# Server_I2C_GND.net
KiCad netlist of a schematic drawn in Altium Designer
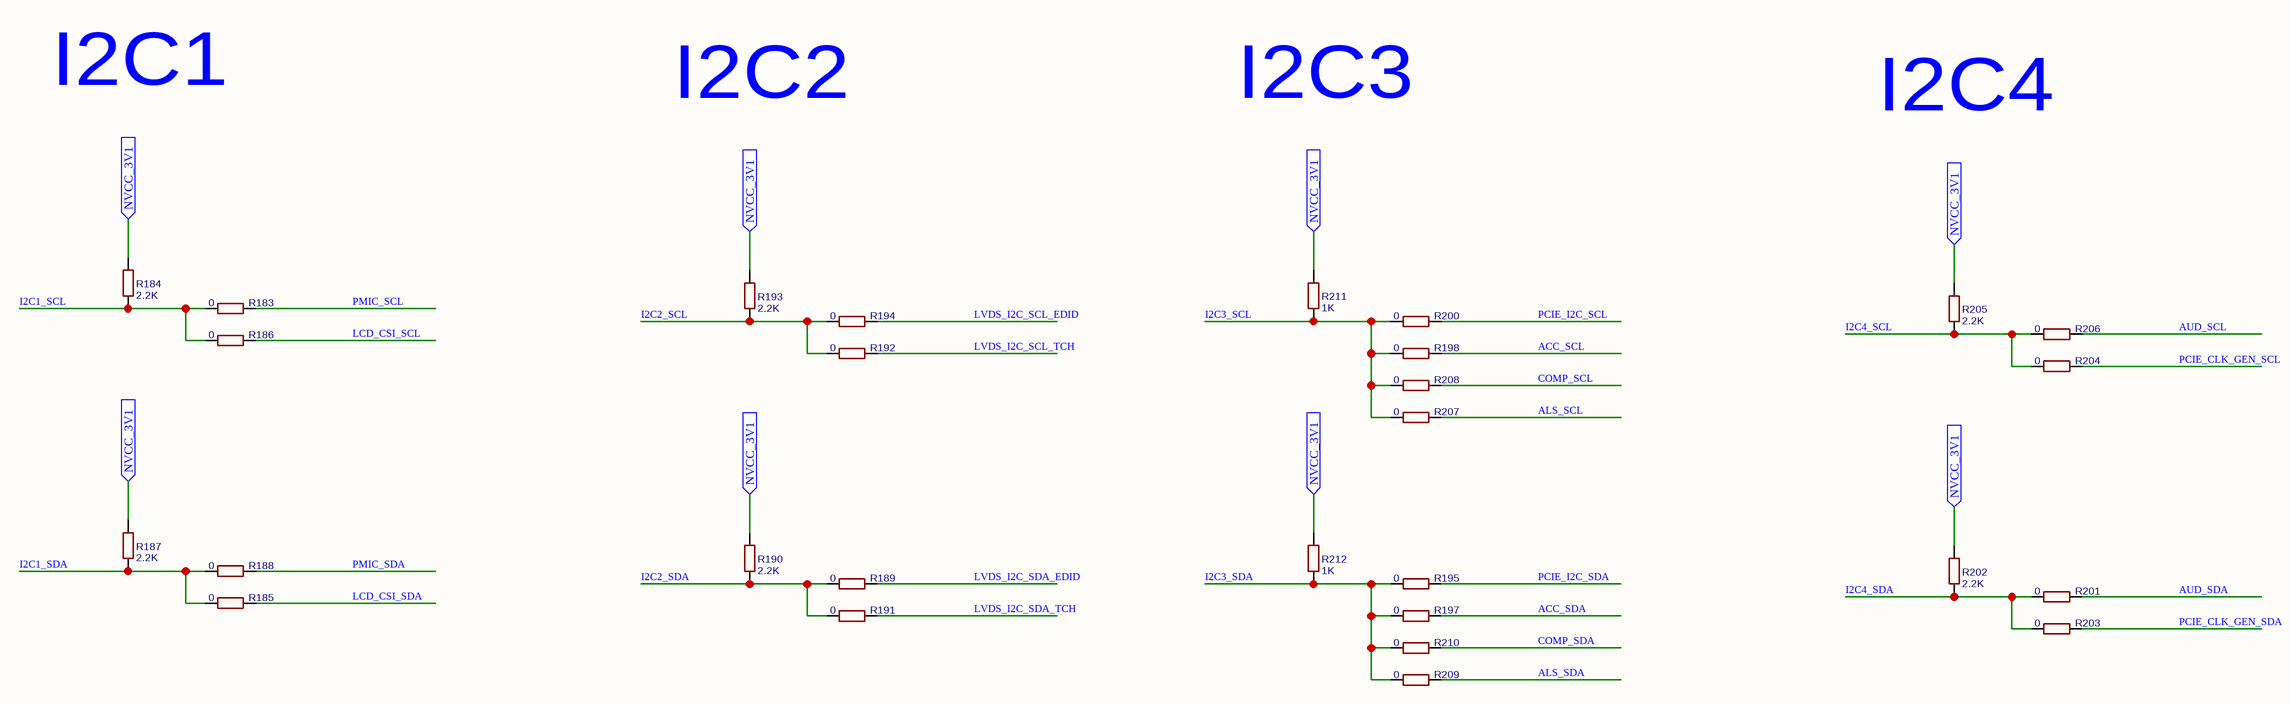
[diagram p0: Server I2C & GND.schdoc]

(export (version "E")
  (design (tool "Eeschema 10.0.6"))
  (components
    (comp (ref "R183")
      (value "0")
      (fields
        (field (name "BOM_MANUFACTURER PART") "RK73Z1ETTP")
        (field (name "BOM_SUPPLIER PART") "C131359")
      )
      (libsource (lib "altium-import") (part "root_0_0_"))
    )
    (comp (ref "R184")
      (value "2.2K")
      (fields
        (field (name "BOM_MANUFACTURER PART") "0402WGF2201TCE")
        (field (name "BOM_SUPPLIER PART") "C25879")
      )
      (libsource (lib "altium-import") (part "root_1_2.2K_"))
    )
    (comp (ref "R185")
      (value "0")
      (fields
        (field (name "BOM_MANUFACTURER PART") "RK73Z1ETTP")
        (field (name "BOM_SUPPLIER PART") "C131359")
      )
      (libsource (lib "altium-import") (part "root_0_0_"))
    )
    (comp (ref "R186")
      (value "0")
      (fields
        (field (name "BOM_MANUFACTURER PART") "RK73Z1ETTP")
        (field (name "BOM_SUPPLIER PART") "C131359")
      )
      (libsource (lib "altium-import") (part "root_0_0_"))
    )
    (comp (ref "R187")
      (value "2.2K")
      (fields
        (field (name "BOM_MANUFACTURER PART") "0402WGF2201TCE")
        (field (name "BOM_SUPPLIER PART") "C25879")
      )
      (libsource (lib "altium-import") (part "root_1_2.2K_"))
    )
    (comp (ref "R188")
      (value "0")
      (fields
        (field (name "BOM_MANUFACTURER PART") "RK73Z1ETTP")
        (field (name "BOM_SUPPLIER PART") "C131359")
      )
      (libsource (lib "altium-import") (part "root_0_0_"))
    )
    (comp (ref "R189")
      (value "0")
      (fields
        (field (name "BOM_MANUFACTURER PART") "RK73Z1ETTP")
        (field (name "BOM_SUPPLIER PART") "C131359")
      )
      (libsource (lib "altium-import") (part "root_0_0_"))
    )
    (comp (ref "R190")
      (value "2.2K")
      (fields
        (field (name "BOM_MANUFACTURER PART") "0402WGF2201TCE")
        (field (name "BOM_SUPPLIER PART") "C25879")
      )
      (libsource (lib "altium-import") (part "root_1_2.2K_"))
    )
    (comp (ref "R191")
      (value "0")
      (fields
        (field (name "BOM_MANUFACTURER PART") "RK73Z1ETTP")
        (field (name "BOM_SUPPLIER PART") "C131359")
      )
      (libsource (lib "altium-import") (part "root_0_0_"))
    )
    (comp (ref "R192")
      (value "0")
      (fields
        (field (name "BOM_MANUFACTURER PART") "RK73Z1ETTP")
        (field (name "BOM_SUPPLIER PART") "C131359")
      )
      (libsource (lib "altium-import") (part "root_0_0_"))
    )
    (comp (ref "R193")
      (value "2.2K")
      (fields
        (field (name "BOM_MANUFACTURER PART") "0402WGF2201TCE")
        (field (name "BOM_SUPPLIER PART") "C25879")
      )
      (libsource (lib "altium-import") (part "root_1_2.2K_"))
    )
    (comp (ref "R194")
      (value "0")
      (fields
        (field (name "BOM_MANUFACTURER PART") "RK73Z1ETTP")
        (field (name "BOM_SUPPLIER PART") "C131359")
      )
      (libsource (lib "altium-import") (part "root_0_0_"))
    )
    (comp (ref "R195")
      (value "0")
      (fields
        (field (name "BOM_MANUFACTURER PART") "RK73Z1ETTP")
        (field (name "BOM_SUPPLIER PART") "C131359")
      )
      (libsource (lib "altium-import") (part "root_0_0_"))
    )
    (comp (ref "R197")
      (value "0")
      (fields
        (field (name "BOM_MANUFACTURER PART") "RK73Z1ETTP")
        (field (name "BOM_SUPPLIER PART") "C131359")
      )
      (libsource (lib "altium-import") (part "root_0_0_"))
    )
    (comp (ref "R198")
      (value "0")
      (fields
        (field (name "BOM_MANUFACTURER PART") "RK73Z1ETTP")
        (field (name "BOM_SUPPLIER PART") "C131359")
      )
      (libsource (lib "altium-import") (part "root_0_0_"))
    )
    (comp (ref "R200")
      (value "0")
      (fields
        (field (name "BOM_MANUFACTURER PART") "RK73Z1ETTP")
        (field (name "BOM_SUPPLIER PART") "C131359")
      )
      (libsource (lib "altium-import") (part "root_0_0_"))
    )
    (comp (ref "R201")
      (value "0")
      (fields
        (field (name "BOM_MANUFACTURER PART") "RK73Z1ETTP")
        (field (name "BOM_SUPPLIER PART") "C131359")
      )
      (libsource (lib "altium-import") (part "root_0_0_"))
    )
    (comp (ref "R202")
      (value "2.2K")
      (fields
        (field (name "BOM_MANUFACTURER PART") "0402WGF2201TCE")
        (field (name "BOM_SUPPLIER PART") "C25879")
      )
      (libsource (lib "altium-import") (part "root_1_2.2K_"))
    )
    (comp (ref "R203")
      (value "0")
      (fields
        (field (name "BOM_MANUFACTURER PART") "RK73Z1ETTP")
        (field (name "BOM_SUPPLIER PART") "C131359")
      )
      (libsource (lib "altium-import") (part "root_0_0_"))
    )
    (comp (ref "R204")
      (value "0")
      (fields
        (field (name "BOM_MANUFACTURER PART") "RK73Z1ETTP")
        (field (name "BOM_SUPPLIER PART") "C131359")
      )
      (libsource (lib "altium-import") (part "root_0_0_"))
    )
    (comp (ref "R205")
      (value "2.2K")
      (fields
        (field (name "BOM_MANUFACTURER PART") "0402WGF2201TCE")
        (field (name "BOM_SUPPLIER PART") "C25879")
      )
      (libsource (lib "altium-import") (part "root_1_2.2K_"))
    )
    (comp (ref "R206")
      (value "0")
      (fields
        (field (name "BOM_MANUFACTURER PART") "RK73Z1ETTP")
        (field (name "BOM_SUPPLIER PART") "C131359")
      )
      (libsource (lib "altium-import") (part "root_0_0_"))
    )
    (comp (ref "R207")
      (value "0")
      (fields
        (field (name "BOM_MANUFACTURER PART") "RK73Z1ETTP")
        (field (name "BOM_SUPPLIER PART") "C131359")
      )
      (libsource (lib "altium-import") (part "root_0_0_"))
    )
    (comp (ref "R208")
      (value "0")
      (fields
        (field (name "BOM_MANUFACTURER PART") "RK73Z1ETTP")
        (field (name "BOM_SUPPLIER PART") "C131359")
      )
      (libsource (lib "altium-import") (part "root_0_0_"))
    )
    (comp (ref "R209")
      (value "0")
      (fields
        (field (name "BOM_MANUFACTURER PART") "RK73Z1ETTP")
        (field (name "BOM_SUPPLIER PART") "C131359")
      )
      (libsource (lib "altium-import") (part "root_0_0_"))
    )
    (comp (ref "R210")
      (value "0")
      (fields
        (field (name "BOM_MANUFACTURER PART") "RK73Z1ETTP")
        (field (name "BOM_SUPPLIER PART") "C131359")
      )
      (libsource (lib "altium-import") (part "root_0_0_"))
    )
    (comp (ref "R211")
      (value "1K")
      (fields
        (field (name "BOM_MANUFACTURER PART") "0402WGF1001TCE")
        (field (name "BOM_SUPPLIER PART") "C11702")
      )
      (libsource (lib "altium-import") (part "root_1_1K_"))
    )
    (comp (ref "R212")
      (value "1K")
      (fields
        (field (name "BOM_MANUFACTURER PART") "0402WGF1001TCE")
        (field (name "BOM_SUPPLIER PART") "C11702")
      )
      (libsource (lib "altium-import") (part "root_1_1K_"))
    )
  )
  (nets
    (net (code "1") (name "/ACC_SCL") (class "Default")
      (node (ref "R198") (pin "2") (pinfunction "2_2") (pintype "passive"))
    )
    (net (code "2") (name "/ACC_SDA") (class "Default")
      (node (ref "R197") (pin "2") (pinfunction "2_2") (pintype "passive"))
    )
    (net (code "3") (name "/ALS_SCL") (class "Default")
      (node (ref "R207") (pin "2") (pinfunction "2_2") (pintype "passive"))
    )
    (net (code "4") (name "/ALS_SDA") (class "Default")
      (node (ref "R209") (pin "2") (pinfunction "2_2") (pintype "passive"))
    )
    (net (code "5") (name "/AUD_SCL") (class "Default")
      (node (ref "R206") (pin "2") (pinfunction "2_2") (pintype "passive"))
    )
    (net (code "6") (name "/AUD_SDA") (class "Default")
      (node (ref "R201") (pin "2") (pinfunction "2_2") (pintype "passive"))
    )
    (net (code "7") (name "/COMP_SCL") (class "Default")
      (node (ref "R208") (pin "2") (pinfunction "2_2") (pintype "passive"))
    )
    (net (code "8") (name "/COMP_SDA") (class "Default")
      (node (ref "R210") (pin "2") (pinfunction "2_2") (pintype "passive"))
    )
    (net (code "9") (name "/I2C1_SCL") (class "Default")
      (node (ref "R183") (pin "1") (pinfunction "1_1") (pintype "passive"))
      (node (ref "R184") (pin "1") (pinfunction "1_1") (pintype "passive"))
      (node (ref "R186") (pin "1") (pinfunction "1_1") (pintype "passive"))
    )
    (net (code "10") (name "/I2C1_SDA") (class "Default")
      (node (ref "R185") (pin "1") (pinfunction "1_1") (pintype "passive"))
      (node (ref "R187") (pin "1") (pinfunction "1_1") (pintype "passive"))
      (node (ref "R188") (pin "1") (pinfunction "1_1") (pintype "passive"))
    )
    (net (code "11") (name "/I2C2_SCL") (class "Default")
      (node (ref "R192") (pin "1") (pinfunction "1_1") (pintype "passive"))
      (node (ref "R193") (pin "1") (pinfunction "1_1") (pintype "passive"))
      (node (ref "R194") (pin "1") (pinfunction "1_1") (pintype "passive"))
    )
    (net (code "12") (name "/I2C2_SDA") (class "Default")
      (node (ref "R189") (pin "1") (pinfunction "1_1") (pintype "passive"))
      (node (ref "R190") (pin "1") (pinfunction "1_1") (pintype "passive"))
      (node (ref "R191") (pin "1") (pinfunction "1_1") (pintype "passive"))
    )
    (net (code "13") (name "/I2C3_SCL") (class "Default")
      (node (ref "R198") (pin "1") (pinfunction "1_1") (pintype "passive"))
      (node (ref "R200") (pin "1") (pinfunction "1_1") (pintype "passive"))
      (node (ref "R207") (pin "1") (pinfunction "1_1") (pintype "passive"))
      (node (ref "R208") (pin "1") (pinfunction "1_1") (pintype "passive"))
      (node (ref "R211") (pin "1") (pinfunction "1_1") (pintype "passive"))
    )
    (net (code "14") (name "/I2C3_SDA") (class "Default")
      (node (ref "R195") (pin "1") (pinfunction "1_1") (pintype "passive"))
      (node (ref "R197") (pin "1") (pinfunction "1_1") (pintype "passive"))
      (node (ref "R209") (pin "1") (pinfunction "1_1") (pintype "passive"))
      (node (ref "R210") (pin "1") (pinfunction "1_1") (pintype "passive"))
      (node (ref "R212") (pin "1") (pinfunction "1_1") (pintype "passive"))
    )
    (net (code "15") (name "/I2C4_SCL") (class "Default")
      (node (ref "R204") (pin "1") (pinfunction "1_1") (pintype "passive"))
      (node (ref "R205") (pin "1") (pinfunction "1_1") (pintype "passive"))
      (node (ref "R206") (pin "1") (pinfunction "1_1") (pintype "passive"))
    )
    (net (code "16") (name "/I2C4_SDA") (class "Default")
      (node (ref "R201") (pin "1") (pinfunction "1_1") (pintype "passive"))
      (node (ref "R202") (pin "1") (pinfunction "1_1") (pintype "passive"))
      (node (ref "R203") (pin "1") (pinfunction "1_1") (pintype "passive"))
    )
    (net (code "17") (name "/LCD_CSI_SCL") (class "Default")
      (node (ref "R186") (pin "2") (pinfunction "2_2") (pintype "passive"))
    )
    (net (code "18") (name "/LCD_CSI_SDA") (class "Default")
      (node (ref "R185") (pin "2") (pinfunction "2_2") (pintype "passive"))
    )
    (net (code "19") (name "/LVDS_I2C_SCL_EDID") (class "Default")
      (node (ref "R194") (pin "2") (pinfunction "2_2") (pintype "passive"))
    )
    (net (code "20") (name "/LVDS_I2C_SCL_TCH") (class "Default")
      (node (ref "R192") (pin "2") (pinfunction "2_2") (pintype "passive"))
    )
    (net (code "21") (name "/LVDS_I2C_SDA_EDID") (class "Default")
      (node (ref "R189") (pin "2") (pinfunction "2_2") (pintype "passive"))
    )
    (net (code "22") (name "/LVDS_I2C_SDA_TCH") (class "Default")
      (node (ref "R191") (pin "2") (pinfunction "2_2") (pintype "passive"))
    )
    (net (code "23") (name "/NVCC_3V1") (class "Default")
      (node (ref "R184") (pin "2") (pinfunction "2_2") (pintype "passive"))
      (node (ref "R187") (pin "2") (pinfunction "2_2") (pintype "passive"))
      (node (ref "R190") (pin "2") (pinfunction "2_2") (pintype "passive"))
      (node (ref "R193") (pin "2") (pinfunction "2_2") (pintype "passive"))
      (node (ref "R202") (pin "2") (pinfunction "2_2") (pintype "passive"))
      (node (ref "R205") (pin "2") (pinfunction "2_2") (pintype "passive"))
      (node (ref "R211") (pin "2") (pinfunction "2_2") (pintype "passive"))
      (node (ref "R212") (pin "2") (pinfunction "2_2") (pintype "passive"))
    )
    (net (code "24") (name "/PCIE_CLK_GEN_SCL") (class "Default")
      (node (ref "R204") (pin "2") (pinfunction "2_2") (pintype "passive"))
    )
    (net (code "25") (name "/PCIE_CLK_GEN_SDA") (class "Default")
      (node (ref "R203") (pin "2") (pinfunction "2_2") (pintype "passive"))
    )
    (net (code "26") (name "/PCIE_I2C_SCL") (class "Default")
      (node (ref "R200") (pin "2") (pinfunction "2_2") (pintype "passive"))
    )
    (net (code "27") (name "/PCIE_I2C_SDA") (class "Default")
      (node (ref "R195") (pin "2") (pinfunction "2_2") (pintype "passive"))
    )
    (net (code "28") (name "/PMIC_SCL") (class "Default")
      (node (ref "R183") (pin "2") (pinfunction "2_2") (pintype "passive"))
    )
    (net (code "29") (name "/PMIC_SDA") (class "Default")
      (node (ref "R188") (pin "2") (pinfunction "2_2") (pintype "passive"))
    )
  )
)
